# BA100_CPU_V1_0.net
KiCad netlist of a schematic drawn in Altium Designer
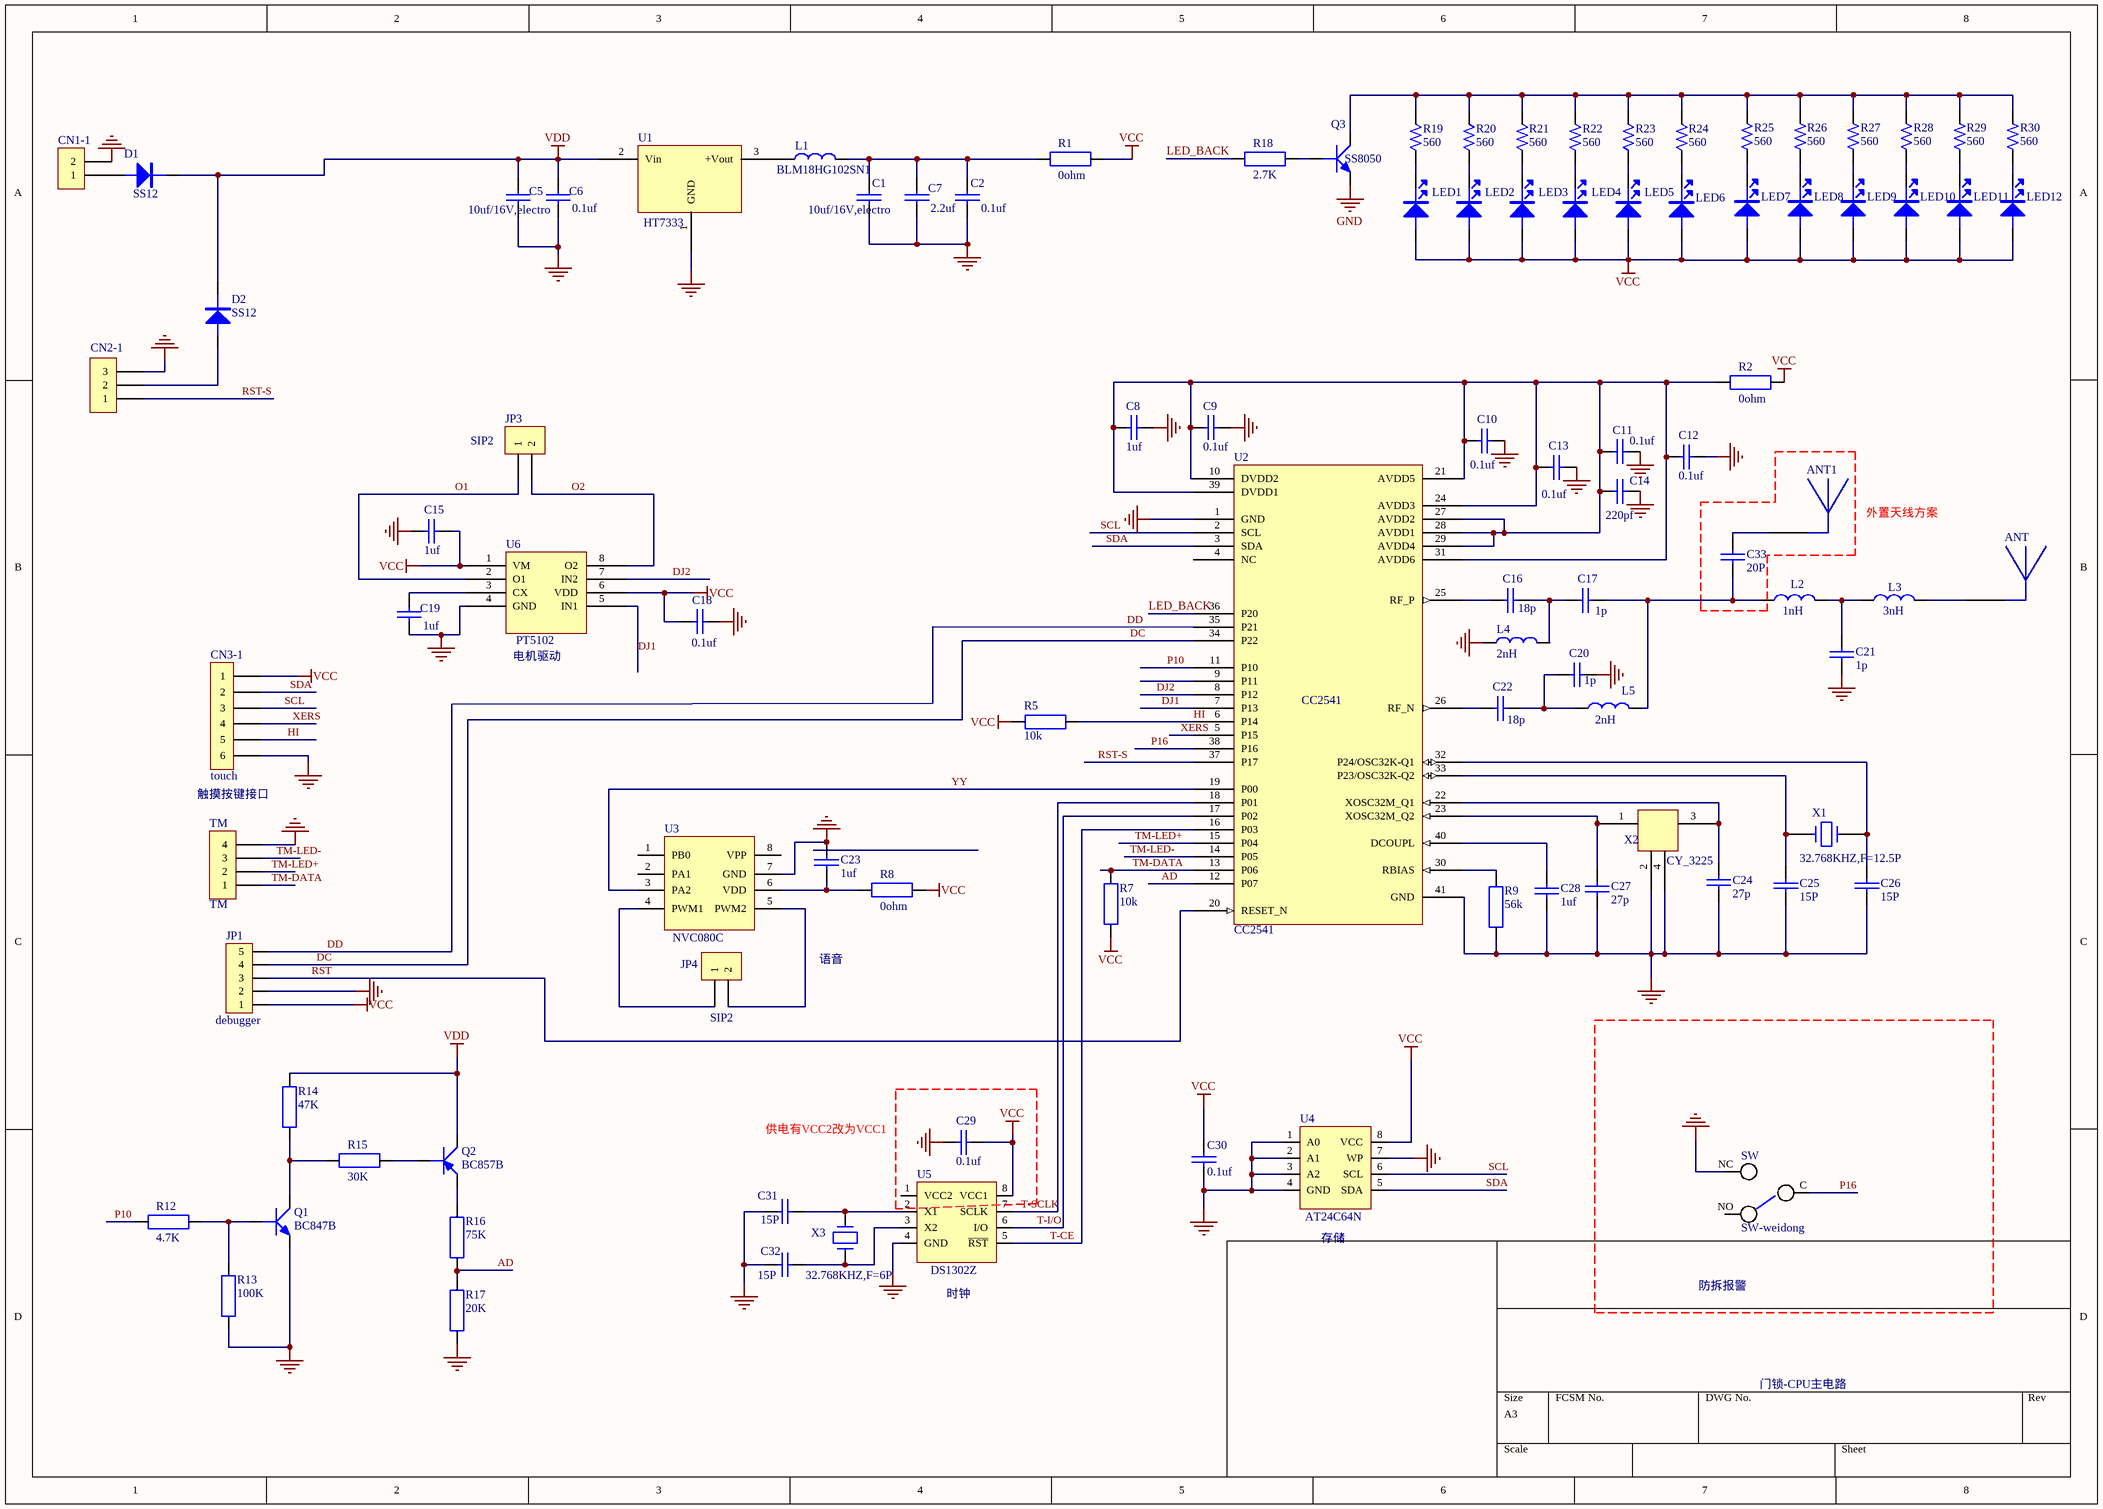
[diagram p0: BA100_CPU_V1.0.SchDoc]

(export (version "E")
  (design (tool "Eeschema 10.0.6"))
  (components
    (comp (ref "ANT") (value "ANT") (footprint "ANT") (libsource (lib "Schlib") (part "ANT")))
    (comp (ref "ANT1") (value "ANT") (footprint "IPEX") (libsource (lib "Schlib") (part "ANT")))
    (comp (ref "C1")
      (value "10uf/16V,electro")
      (footprint "ECAP_10U_4.3*4.3")
      (description "PC7-*****-KQA0A")
      (libsource (lib "Schlib") (part "PC7_0402_YAGEO"))
    )
    (comp (ref "C2")
      (value "0.1uf")
      (footprint "PCB标准封装库:PC7-*****-KO-0A_0603_TDK")
      (description "PC7-*****-KQA0A")
      (libsource (lib "Schlib") (part "PC7_0402_YAGEO"))
    )
    (comp (ref "C5")
      (value "10uf/16V,electro")
      (footprint "ECAP_10U_4.3*4.3")
      (description "PC7-*****-KQA0A")
      (libsource (lib "Schlib") (part "PC7_0402_YAGEO"))
    )
    (comp (ref "C6")
      (value "0.1uf")
      (footprint "PCB标准封装库:PC5-*****-**-0A_0603_TDK")
      (description "PC7-*****-KQA0A")
      (libsource (lib "Schlib") (part "PC7_0402_YAGEO"))
    )
    (comp (ref "C7")
      (value "2.2uf")
      (footprint "PCB标准封装库:PC5-*****-**-0A_0603_TDK")
      (description "PC7-*****-KQA0A")
      (libsource (lib "Schlib") (part "PC7_0402_YAGEO"))
    )
    (comp (ref "C8")
      (value "1uf")
      (footprint "PC5-*****-**-0A_0603_TDK")
      (description "PC7-*****-KQA0A")
      (libsource (lib "Schlib") (part "PC7_0402_YAGEO"))
    )
    (comp (ref "C9")
      (value "0.1uf")
      (footprint "PC7-*****-KO-0A_0603_TDK")
      (description "PC7-*****-KQA0A")
      (libsource (lib "Schlib") (part "PC7_0402_YAGEO"))
    )
    (comp (ref "C10")
      (value "0.1uf")
      (footprint "PC5-*****-**-0A_0603_TDK")
      (description "PC7-*****-KQA0A")
      (libsource (lib "Schlib") (part "PC7_0402_YAGEO"))
    )
    (comp (ref "C11")
      (value "0.1uf")
      (footprint "PC7-*****-KQA0A_0402_YAGEO")
      (description "PC7-*****-KQA0A")
      (libsource (lib "Schlib") (part "PC7_0402_YAGEO"))
    )
    (comp (ref "C12")
      (value "0.1uf")
      (footprint "PC7-*****-KQA0A_0402_YAGEO")
      (description "PC7-*****-KQA0A")
      (libsource (lib "Schlib") (part "PC7_0402_YAGEO"))
    )
    (comp (ref "C13")
      (value "0.1uf")
      (footprint "PC7-*****-KQA0A_0402_YAGEO")
      (description "PC7-*****-KQA0A")
      (libsource (lib "Schlib") (part "PC7_0402_YAGEO"))
    )
    (comp (ref "C14")
      (value "220pf")
      (footprint "PC7-*****-KQA0A_0402_YAGEO")
      (description "PC7-*****-KQA0A")
      (libsource (lib "Schlib") (part "PC7_0402_YAGEO"))
    )
    (comp (ref "C15")
      (value "1uf")
      (footprint "PCB标准封装库:PC5-*****-**-0A_0603_TDK")
      (description "PC7-*****-KQA0A")
      (libsource (lib "Schlib") (part "PC7_0402_YAGEO"))
    )
    (comp (ref "C16")
      (value "18p")
      (footprint "PC7-*****-KQA0A_0402_YAGEO")
      (description "PC7-*****-KQA0A")
      (libsource (lib "Schlib") (part "PC7_0402_YAGEO"))
    )
    (comp (ref "C17")
      (value "1p")
      (footprint "PC7-*****-KQA0A_0402_YAGEO")
      (description "PC7-*****-KQA0A")
      (libsource (lib "Schlib") (part "PC7_0402_YAGEO"))
    )
    (comp (ref "C18")
      (value "0.1uf")
      (footprint "PCB标准封装库:PC5-*****-**-0A_0603_TDK")
      (description "PC7-*****-KQA0A")
      (libsource (lib "Schlib") (part "PC7_0402_YAGEO"))
    )
    (comp (ref "C19")
      (value "1uf")
      (footprint "PCB标准封装库:PC5-*****-**-0A_0603_TDK")
      (description "PC7-*****-KQA0A")
      (libsource (lib "Schlib") (part "PC7_0402_YAGEO"))
    )
    (comp (ref "C20")
      (value "1p")
      (footprint "PC7-*****-KQA0A_0402_YAGEO")
      (description "PC7-*****-KQA0A")
      (libsource (lib "Schlib") (part "PC7_0402_YAGEO"))
    )
    (comp (ref "C21")
      (value "1p")
      (footprint "PC7-*****-KQA0A_0402_YAGEO")
      (description "PC7-*****-KQA0A")
      (libsource (lib "Schlib") (part "PC7_0402_YAGEO"))
    )
    (comp (ref "C22")
      (value "18p")
      (footprint "PC7-*****-KQA0A_0402_YAGEO")
      (description "PC7-*****-KQA0A")
      (libsource (lib "Schlib") (part "PC7_0402_YAGEO"))
    )
    (comp (ref "C23")
      (value "1uf")
      (footprint "PCB标准封装库:PC5-*****-**-0A_0603_TDK")
      (description "PC7-*****-KQA0A")
      (libsource (lib "Schlib") (part "PC7_0402_YAGEO"))
    )
    (comp (ref "C24")
      (value "27p")
      (footprint "PC7-*****-KO-0A_0603_TDK")
      (description "PC7-*****-KQA0A")
      (libsource (lib "Schlib") (part "PC7_0402_YAGEO"))
    )
    (comp (ref "C25")
      (value "15P")
      (footprint "PC5-*****-**-0A_0603_TDK")
      (description "PC7-*****-KQA0A")
      (libsource (lib "Schlib") (part "PC7_0402_YAGEO"))
    )
    (comp (ref "C26")
      (value "15P")
      (footprint "PC7-*****-KO-0A_0603_TDK")
      (description "PC7-*****-KQA0A")
      (libsource (lib "Schlib") (part "PC7_0402_YAGEO"))
    )
    (comp (ref "C27")
      (value "27p")
      (footprint "PC7-*****-KO-0A_0603_TDK")
      (description "PC7-*****-KQA0A")
      (libsource (lib "Schlib") (part "PC7_0402_YAGEO"))
    )
    (comp (ref "C28")
      (value "1uf")
      (footprint "PC5-*****-**-0A_0603_TDK")
      (description "PC7-*****-KQA0A")
      (libsource (lib "Schlib") (part "PC7_0402_YAGEO"))
    )
    (comp (ref "C29")
      (value "0.1uf")
      (footprint "PC7-*****-KO-0A_0603_TDK")
      (description "PC7-*****-KQA0A")
      (libsource (lib "Schlib") (part "PC7_0402_YAGEO"))
    )
    (comp (ref "C30")
      (value "0.1uf")
      (footprint "PC5-*****-**-0A_0603_TDK")
      (description "PC7-*****-KQA0A")
      (libsource (lib "Schlib") (part "PC7_0402_YAGEO"))
    )
    (comp (ref "C31")
      (value "15P")
      (footprint "PC7-*****-KO-0A_0603_TDK")
      (description "PC7-*****-KQA0A")
      (libsource (lib "Schlib") (part "PC7_0402_YAGEO"))
    )
    (comp (ref "C32")
      (value "15P")
      (footprint "PC7-*****-KO-0A_0603_TDK")
      (description "PC7-*****-KQA0A")
      (libsource (lib "Schlib") (part "PC7_0402_YAGEO"))
    )
    (comp (ref "C33")
      (value "20P")
      (footprint "PC7-*****-KQA0A_0402_YAGEO")
      (description "PC7-*****-KQA0A")
      (libsource (lib "Schlib") (part "PC7_0402_YAGEO"))
    )
    (comp (ref "CN1-1")
      (value "CN1")
      (footprint "PH2.0-2PIN-SMT")
      (description "Connector")
      (libsource (lib "") (part "CON2_1"))
    )
    (comp (ref "CN2-1")
      (value "CN2")
      (footprint "BJC:PH2.0-3PIN-SMT")
      (fields (field (name "PUBLISHER") "Altium Limited"))
      (libsource (lib "Schlib") (part "JP1_E524.03"))
    )
    (comp (ref "CN3-1") (value "touch") (footprint "PH1.25-6PIN-SMT") (libsource (lib "*") (part "CON6")))
    (comp (ref "D1")
      (value "SS12")
      (footprint "SS12-DIDEO")
      (description "PDD-00330-00-2A")
      (libsource (lib "*") (part "PDD_SD101CWS"))
    )
    (comp (ref "D2")
      (value "SS12")
      (footprint "SS12-DIDEO")
      (description "PDD-00330-00-2A")
      (libsource (lib "*") (part "PDD_SD101CWS"))
    )
    (comp (ref "JP1") (value "debugger") (footprint "ISCP-5PIN") (libsource (lib "BJC") (part "CON5")))
    (comp (ref "JP3")
      (value "SIP2")
      (footprint "PH2.0-2PIN-LSMT1")
      (description "Connector")
      (libsource (lib "BJC") (part "CON2"))
    )
    (comp (ref "JP4")
      (value "SIP2")
      (footprint "PH2.0-2PIN-LSMT1")
      (description "Connector")
      (libsource (lib "BJC") (part "CON2"))
    )
    (comp (ref "L1")
      (value "BLM18HG102SN1")
      (footprint "PCB标准封装库:PC7-*****-KO-0A_0603_TDK")
      (description "PWL-00195-00-20")
      (libsource (lib "Schlib") (part "PWL_18nH"))
    )
    (comp (ref "L2")
      (value "1nH")
      (footprint "PC5-*****-**-0A_0402_TDK")
      (description "PWL-00195-00-20")
      (libsource (lib "Schlib") (part "PWL_18nH"))
    )
    (comp (ref "L3")
      (value "3nH")
      (footprint "PCB标准封装库:PC5-*****-**-0A_0402_TDK")
      (description "PWL-00195-00-20")
      (libsource (lib "Schlib") (part "PWL_18nH"))
    )
    (comp (ref "L4")
      (value "2nH")
      (footprint "PC5-*****-**-0A_0402_TDK")
      (description "PWL-00195-00-20")
      (libsource (lib "Schlib") (part "PWL_18nH"))
    )
    (comp (ref "L5")
      (value "2nH")
      (footprint "PC5-*****-**-0A_0402_TDK")
      (description "PWL-00195-00-20")
      (libsource (lib "Schlib") (part "PWL_18nH"))
    )
    (comp (ref "LED1")
      (value "MA2X335")
      (footprint "PCB_100:LED-0805")
      (description "LED")
      (libsource (lib "PCB_BA100") (part "PDD_MA2X335"))
    )
    (comp (ref "LED2")
      (value "MA2X335")
      (footprint "PCB_100:LED-0805")
      (description "LED")
      (libsource (lib "PCB_BA100") (part "PDD_MA2X335"))
    )
    (comp (ref "LED3")
      (value "MA2X335")
      (footprint "PCB_100:LED-0805")
      (description "LED")
      (libsource (lib "PCB_BA100") (part "PDD_MA2X335"))
    )
    (comp (ref "LED4")
      (value "MA2X335")
      (footprint "PCB_100:LED-0805")
      (description "LED")
      (libsource (lib "PCB_BA100") (part "PDD_MA2X335"))
    )
    (comp (ref "LED5")
      (value "MA2X335")
      (footprint "PCB_100:LED-0805")
      (description "LED")
      (libsource (lib "PCB_BA100") (part "PDD_MA2X335"))
    )
    (comp (ref "LED6")
      (value "MA2X335")
      (footprint "PCB_100:LED-0805")
      (description "LED")
      (libsource (lib "PCB_BA100") (part "PDD_MA2X335"))
    )
    (comp (ref "LED7")
      (value "MA2X335")
      (footprint "BA100_CPU_V1.5.1:LED-0805")
      (description "LED")
      (libsource (lib "BA100_CPU_1.5.1") (part "PDD_MA2X335"))
    )
    (comp (ref "LED8")
      (value "MA2X335")
      (footprint "BA100_CPU_V1.5.1:LED-0805")
      (description "LED")
      (libsource (lib "BA100_CPU_1.5.1") (part "PDD_MA2X335"))
    )
    (comp (ref "LED9")
      (value "MA2X335")
      (footprint "BA100_CPU_V1.5.1:LED-0805")
      (description "LED")
      (libsource (lib "BA100_CPU_1.5.1") (part "PDD_MA2X335"))
    )
    (comp (ref "LED10")
      (value "MA2X335")
      (footprint "BA100_CPU_V1.5.1:LED-0805")
      (description "LED")
      (libsource (lib "BA100_CPU_1.5.1") (part "PDD_MA2X335"))
    )
    (comp (ref "LED11")
      (value "MA2X335")
      (footprint "BA100_CPU_V1.5.1:LED-0805")
      (description "LED")
      (libsource (lib "BA100_CPU_1.5.1") (part "PDD_MA2X335"))
    )
    (comp (ref "LED12")
      (value "MA2X335")
      (footprint "BA100_CPU_V1.5.1:LED-0805")
      (description "LED")
      (libsource (lib "BA100_CPU_1.5.1") (part "PDD_MA2X335"))
    )
    (comp (ref "Q1")
      (value "BC847B")
      (footprint "PTR-C0025-00-2A_2SC1623")
      (description "PTR-C0028-00-2A")
      (libsource (lib "Schlib") (part "PTR_2SC3356"))
    )
    (comp (ref "Q2")
      (value "BC857B")
      (footprint "PTR-C0025-00-2A_2SC1623")
      (libsource (lib "*") (part "PTR-PNP"))
    )
    (comp (ref "Q3")
      (value "SS8050")
      (footprint "BA100_CPU_V1.4.0:PTR-C0025-00-2A_2SC1623")
      (description "PTR-C0230-00-20**")
      (libsource (lib "Schlib") (part "PTR_2SC5344SF-Y"))
    )
    (comp (ref "R1")
      (value "0ohm")
      (footprint "PCB标准封装库:PRC-*****-AM-0A_0603")
      (description "PRC-*****-AM-0A_0603")
      (libsource (lib "Schlib") (part "PRC_0603"))
    )
    (comp (ref "R2")
      (value "0ohm")
      (footprint "PRC-*****-AM-0A_0603")
      (description "PRC-*****-AM-0A_0603")
      (libsource (lib "Schlib") (part "PRC_0603"))
    )
    (comp (ref "R5")
      (value "10k")
      (footprint "PCB标准封装库:PRC-*****-AM-0A_0603")
      (description "PRC-*****-AM-0A_0603")
      (libsource (lib "Schlib") (part "PRC_0603"))
    )
    (comp (ref "R7")
      (value "10k")
      (footprint "PCB标准封装库:PRC-*****-AM-0A_0603")
      (description "PRC-*****-AM-0A_0603")
      (libsource (lib "Schlib") (part "PRC_0603"))
    )
    (comp (ref "R8")
      (value "0ohm")
      (footprint "PCB标准封装库:PRC-*****-AM-0A_0603")
      (description "PRC-*****-AM-0A_0603")
      (libsource (lib "Schlib") (part "PRC_0603"))
    )
    (comp (ref "R9")
      (value "56k")
      (footprint "PRC-*****-BM-0A_0402")
      (description "PRC-*****-AM-0A_0603")
      (libsource (lib "Schlib") (part "PRC_0603"))
    )
    (comp (ref "R12")
      (value "4.7K")
      (footprint "PCB标准封装库:PRC-*****-AM-0A_0603")
      (description "PRC-*****-AM-0A_0603")
      (libsource (lib "Schlib") (part "PRC_0603"))
    )
    (comp (ref "R13")
      (value "100K")
      (footprint "PCB标准封装库:PRC-*****-AM-0A_0603")
      (description "PRC-*****-AM-0A_0603")
      (libsource (lib "Schlib") (part "PRC_0603"))
    )
    (comp (ref "R14")
      (value "47K")
      (footprint "PCB标准封装库:PRC-*****-AM-0A_0603")
      (description "PRC-*****-AM-0A_0603")
      (libsource (lib "Schlib") (part "PRC_0603"))
    )
    (comp (ref "R15")
      (value "30K")
      (footprint "BA100_CPU_V1.4.0:PRC-*****-AM-0A_0603")
      (description "PRC-*****-AM-0A_0603")
      (libsource (lib "Schlib") (part "PRC_0603"))
    )
    (comp (ref "R16")
      (value "75K")
      (footprint "PCB标准封装库:PRC-*****-AM-0A_0603")
      (description "PRC-*****-AM-0A_0603")
      (libsource (lib "Schlib") (part "PRC_0603"))
    )
    (comp (ref "R17")
      (value "20K")
      (footprint "PCB标准封装库:PRC-*****-AM-0A_0603")
      (description "PRC-*****-AM-0A_0603")
      (libsource (lib "Schlib") (part "PRC_0603"))
    )
    (comp (ref "R18")
      (value "2.7K")
      (footprint "BA100_CPU_V1.4.0:PRC-*****-AM-0A_0603")
      (description "PRC-*****-AM-0A_0603")
      (libsource (lib "Schlib") (part "PRC_0603"))
    )
    (comp (ref "R19")
      (value "560")
      (footprint "PRC-*****-AM-0A_0603")
      (libsource (lib "PCB_BA100") (part "RES"))
    )
    (comp (ref "R20")
      (value "560")
      (footprint "PRC-*****-AM-0A_0603")
      (libsource (lib "PCB_BA100") (part "RES"))
    )
    (comp (ref "R21")
      (value "560")
      (footprint "PRC-*****-AM-0A_0603")
      (libsource (lib "PCB_BA100") (part "RES"))
    )
    (comp (ref "R22")
      (value "560")
      (footprint "PRC-*****-AM-0A_0603")
      (libsource (lib "PCB_BA100") (part "RES"))
    )
    (comp (ref "R23")
      (value "560")
      (footprint "PRC-*****-AM-0A_0603")
      (libsource (lib "PCB_BA100") (part "RES"))
    )
    (comp (ref "R24")
      (value "560")
      (footprint "PRC-*****-AM-0A_0603")
      (libsource (lib "PCB_BA100") (part "RES"))
    )
    (comp (ref "R25")
      (value "560")
      (footprint "BA100_CPU_V1.5.1:PRC-*****-AM-0A_0603")
      (libsource (lib "BA100_CPU_1.5.1") (part "RES"))
    )
    (comp (ref "R26")
      (value "560")
      (footprint "BA100_CPU_V1.5.1:PRC-*****-AM-0A_0603")
      (libsource (lib "BA100_CPU_1.5.1") (part "RES"))
    )
    (comp (ref "R27")
      (value "560")
      (footprint "BA100_CPU_V1.5.1:PRC-*****-AM-0A_0603")
      (libsource (lib "BA100_CPU_1.5.1") (part "RES"))
    )
    (comp (ref "R28")
      (value "560")
      (footprint "BA100_CPU_V1.5.1:PRC-*****-AM-0A_0603")
      (libsource (lib "BA100_CPU_1.5.1") (part "RES"))
    )
    (comp (ref "R29")
      (value "560")
      (footprint "BA100_CPU_V1.5.1:PRC-*****-AM-0A_0603")
      (libsource (lib "BA100_CPU_1.5.1") (part "RES"))
    )
    (comp (ref "R30")
      (value "560")
      (footprint "BA100_CPU_V1.5.1:PRC-*****-AM-0A_0603")
      (libsource (lib "BA100_CPU_1.5.1") (part "RES"))
    )
    (comp (ref "SW")
      (value "SW-weidong")
      (footprint "SW-weidong")
      (libsource (lib "PCB_BA100_MAIN_1.5.1") (part "SW-weidong"))
    )
    (comp (ref "TM") (value "TM") (footprint "PH2.0-4PIN-SMT") (libsource (lib "Schlib") (part "HDR1X4 ***")))
    (comp (ref "U1") (value "HT7333") (footprint "SOT89") (libsource (lib "*") (part "LM117K")))
    (comp (ref "U2") (value "CC2541") (footprint "CC2530_QFN40") (libsource (lib "*") (part "CC2541")))
    (comp (ref "U3") (value "NVC080C") (footprint "SOP-8") (libsource (lib "BJC") (part "NV040C")))
    (comp (ref "U4")
      (value "AT24C64N")
      (footprint "PIC-00570-40-2A_93LC46B")
      (libsource (lib "BJC") (part "AT24C64N"))
    )
    (comp (ref "U5")
      (value "DS1302Z")
      (footprint "PIC-00570-40-2A_93LC46B")
      (libsource (lib "BJC") (part "DS1302"))
    )
    (comp (ref "U6") (value "PT5102") (footprint "PT5102") (libsource (lib "BJC") (part "Component_1_1")))
    (comp (ref "X1")
      (value "32.768KHZ,F=12.5P")
      (footprint "FC-135")
      (description "Crystal")
      (libsource (lib "CC254xEM原理图库") (part "CRYSTAL"))
    )
    (comp (ref "X2")
      (value "CY_3225")
      (footprint "CY_3225")
      (libsource (lib "CC254xEM原理图库") (part "CY_3225"))
    )
    (comp (ref "X3")
      (value "32.768KHZ,F=6P")
      (footprint "GUASUO-V1.3-151210:FC-135")
      (description "PTR-X0320-20-2A")
      (libsource (lib "BJC") (part "PTR_16MHZ"))
    )
  )
  (nets
    (net (code "1") (name "/AD") (class "Default")
      (node (ref "R16") (pin "1") (pinfunction "1_1") (pintype "passive"))
      (node (ref "R17") (pin "2") (pinfunction "2_2") (pintype "passive"))
      (node (ref "U2") (pin "12") (pinfunction "P07_12") (pintype "passive"))
    )
    (net (code "2") (name "/DC") (class "Default")
      (node (ref "JP1") (pin "4") (pinfunction "4_4") (pintype "passive"))
      (node (ref "U2") (pin "34") (pinfunction "P22_34") (pintype "passive"))
    )
    (net (code "3") (name "/DD") (class "Default")
      (node (ref "JP1") (pin "5") (pinfunction "5_5") (pintype "passive"))
      (node (ref "U2") (pin "35") (pinfunction "P21_35") (pintype "passive"))
    )
    (net (code "4") (name "/DJ1") (class "Default")
      (node (ref "U2") (pin "7") (pinfunction "P13_7") (pintype "passive"))
      (node (ref "U6") (pin "5") (pinfunction "IN1_5") (pintype "passive"))
    )
    (net (code "5") (name "/DJ2") (class "Default")
      (node (ref "U2") (pin "8") (pinfunction "P12_8") (pintype "passive"))
      (node (ref "U6") (pin "7") (pinfunction "IN2_7") (pintype "passive"))
    )
    (net (code "6") (name "/HI") (class "Default")
      (node (ref "CN3-1") (pin "5") (pinfunction "5_5") (pintype "passive"))
      (node (ref "R5") (pin "2") (pinfunction "2_2") (pintype "passive"))
      (node (ref "U2") (pin "6") (pinfunction "P14_6") (pintype "passive"))
    )
    (net (code "7") (name "/LED_BACK") (class "Default")
      (node (ref "R18") (pin "1") (pinfunction "1_1") (pintype "passive"))
      (node (ref "U2") (pin "36") (pinfunction "P20_36") (pintype "passive"))
    )
    (net (code "8") (name "/O1") (class "Default")
      (node (ref "JP3") (pin "1") (pinfunction "1_1") (pintype "passive"))
      (node (ref "U6") (pin "2") (pinfunction "O1_2") (pintype "passive"))
    )
    (net (code "9") (name "/O2") (class "Default")
      (node (ref "JP3") (pin "2") (pinfunction "2_2") (pintype "passive"))
      (node (ref "U6") (pin "8") (pinfunction "O2_8") (pintype "passive"))
    )
    (net (code "10") (name "/P10") (class "Default")
      (node (ref "R12") (pin "1") (pinfunction "1_1") (pintype "passive"))
      (node (ref "U2") (pin "11") (pinfunction "P10_11") (pintype "passive"))
    )
    (net (code "11") (name "/P16") (class "Default")
      (node (ref "SW") (pin "C") (pinfunction "1_C") (pintype "passive"))
      (node (ref "U2") (pin "38") (pinfunction "P16_38") (pintype "passive"))
    )
    (net (code "12") (name "/RST") (class "Default")
      (node (ref "JP1") (pin "3") (pinfunction "3_3") (pintype "passive"))
      (node (ref "U2") (pin "20") (pinfunction "RESET_N_20") (pintype "input"))
    )
    (net (code "13") (name "/RST-S") (class "Default")
      (node (ref "CN2-1") (pin "1") (pinfunction "1_1") (pintype "passive"))
      (node (ref "U2") (pin "37") (pinfunction "P17_37") (pintype "passive"))
    )
    (net (code "14") (name "/SCL") (class "Default")
      (node (ref "CN3-1") (pin "3") (pinfunction "3_3") (pintype "passive"))
      (node (ref "U2") (pin "2") (pinfunction "SCL_2") (pintype "power_in"))
      (node (ref "U4") (pin "6") (pinfunction "SCL_6") (pintype "passive"))
    )
    (net (code "15") (name "/SDA") (class "Default")
      (node (ref "CN3-1") (pin "2") (pinfunction "2_2") (pintype "passive"))
      (node (ref "U2") (pin "3") (pinfunction "SDA_3") (pintype "power_in"))
      (node (ref "U4") (pin "5") (pinfunction "SDA_5") (pintype "passive"))
    )
    (net (code "16") (name "/T-CE") (class "Default")
      (node (ref "U2") (pin "16") (pinfunction "P03_16") (pintype "passive"))
      (node (ref "U5") (pin "5") (pinfunction "~{RST}_5") (pintype "passive"))
    )
    (net (code "17") (name "/T-I{slash}O") (class "Default")
      (node (ref "U2") (pin "17") (pinfunction "P02_17") (pintype "passive"))
      (node (ref "U5") (pin "6") (pinfunction "I/O_6") (pintype "passive"))
    )
    (net (code "18") (name "/T-SCLK") (class "Default")
      (node (ref "U2") (pin "18") (pinfunction "P01_18") (pintype "passive"))
      (node (ref "U5") (pin "7") (pinfunction "SCLK_7") (pintype "passive"))
    )
    (net (code "19") (name "/TM-DATA") (class "Default")
      (node (ref "R7") (pin "2") (pinfunction "2_2") (pintype "passive"))
      (node (ref "TM") (pin "1") (pinfunction "1_1") (pintype "passive"))
      (node (ref "U2") (pin "13") (pinfunction "P06_13") (pintype "passive"))
    )
    (net (code "20") (name "/TM-LED+") (class "Default")
      (node (ref "TM") (pin "2") (pinfunction "2_2") (pintype "passive"))
      (node (ref "U2") (pin "15") (pinfunction "P04_15") (pintype "passive"))
    )
    (net (code "21") (name "/TM-LED-") (class "Default")
      (node (ref "TM") (pin "3") (pinfunction "3_3") (pintype "passive"))
      (node (ref "U2") (pin "14") (pinfunction "P05_14") (pintype "passive"))
    )
    (net (code "22") (name "/XERS") (class "Default")
      (node (ref "CN3-1") (pin "4") (pinfunction "4_4") (pintype "passive"))
      (node (ref "U2") (pin "5") (pinfunction "P15_5") (pintype "passive"))
    )
    (net (code "23") (name "/YY") (class "Default")
      (node (ref "U2") (pin "19") (pinfunction "P00_19") (pintype "passive"))
      (node (ref "U3") (pin "3") (pinfunction "PA2_3") (pintype "passive"))
    )
    (net (code "24") (name "GND") (class "Default")
      (node (ref "C1") (pin "1") (pinfunction "1_1") (pintype "passive"))
      (node (ref "C10") (pin "2") (pinfunction "2_2") (pintype "passive"))
      (node (ref "C11") (pin "2") (pinfunction "2_2") (pintype "passive"))
      (node (ref "C12") (pin "2") (pinfunction "2_2") (pintype "passive"))
      (node (ref "C13") (pin "2") (pinfunction "2_2") (pintype "passive"))
      (node (ref "C14") (pin "1") (pinfunction "1_1") (pintype "passive"))
      (node (ref "C15") (pin "1") (pinfunction "1_1") (pintype "passive"))
      (node (ref "C18") (pin "1") (pinfunction "1_1") (pintype "passive"))
      (node (ref "C19") (pin "1") (pinfunction "1_1") (pintype "passive"))
      (node (ref "C2") (pin "1") (pinfunction "1_1") (pintype "passive"))
      (node (ref "C20") (pin "2") (pinfunction "2_2") (pintype "passive"))
      (node (ref "C21") (pin "1") (pinfunction "1_1") (pintype "passive"))
      (node (ref "C23") (pin "2") (pinfunction "2_2") (pintype "passive"))
      (node (ref "C24") (pin "1") (pinfunction "1_1") (pintype "passive"))
      (node (ref "C25") (pin "1") (pinfunction "1_1") (pintype "passive"))
      (node (ref "C26") (pin "1") (pinfunction "1_1") (pintype "passive"))
      (node (ref "C27") (pin "1") (pinfunction "1_1") (pintype "passive"))
      (node (ref "C28") (pin "1") (pinfunction "1_1") (pintype "passive"))
      (node (ref "C29") (pin "2") (pinfunction "2_2") (pintype "passive"))
      (node (ref "C30") (pin "1") (pinfunction "1_1") (pintype "passive"))
      (node (ref "C31") (pin "2") (pinfunction "2_2") (pintype "passive"))
      (node (ref "C32") (pin "2") (pinfunction "2_2") (pintype "passive"))
      (node (ref "C5") (pin "1") (pinfunction "1_1") (pintype "passive"))
      (node (ref "C6") (pin "1") (pinfunction "1_1") (pintype "passive"))
      (node (ref "C7") (pin "2") (pinfunction "2_2") (pintype "passive"))
      (node (ref "C8") (pin "2") (pinfunction "2_2") (pintype "passive"))
      (node (ref "C9") (pin "2") (pinfunction "2_2") (pintype "passive"))
      (node (ref "CN1-1") (pin "2") (pinfunction "2_2") (pintype "passive"))
      (node (ref "CN2-1") (pin "3") (pinfunction "3_3") (pintype "passive"))
      (node (ref "CN3-1") (pin "6") (pinfunction "6_6") (pintype "passive"))
      (node (ref "JP1") (pin "2") (pinfunction "2_2") (pintype "passive"))
      (node (ref "L4") (pin "1") (pintype "passive"))
      (node (ref "Q1") (pin "E") (pinfunction "1_E") (pintype "passive"))
      (node (ref "Q3") (pin "E") (pinfunction "2_E") (pintype "passive"))
      (node (ref "R13") (pin "1") (pinfunction "1_1") (pintype "passive"))
      (node (ref "R17") (pin "1") (pinfunction "1_1") (pintype "passive"))
      (node (ref "R9") (pin "2") (pinfunction "2_2") (pintype "passive"))
      (node (ref "SW") (pin "NC") (pinfunction "3_NC") (pintype "passive"))
      (node (ref "TM") (pin "4") (pinfunction "4_4") (pintype "passive"))
      (node (ref "U1") (pin "1") (pinfunction "GND_1") (pintype "passive"))
      (node (ref "U2") (pin "1") (pinfunction "GND_1") (pintype "power_in"))
      (node (ref "U2") (pin "41") (pinfunction "GND_41") (pintype "power_in"))
      (node (ref "U3") (pin "7") (pinfunction "GND_7") (pintype "passive"))
      (node (ref "U4") (pin "1") (pinfunction "A0_1") (pintype "passive"))
      (node (ref "U4") (pin "2") (pinfunction "A1_2") (pintype "passive"))
      (node (ref "U4") (pin "3") (pinfunction "A2_3") (pintype "passive"))
      (node (ref "U4") (pin "4") (pinfunction "GND_4") (pintype "passive"))
      (node (ref "U4") (pin "7") (pinfunction "WP_7") (pintype "passive"))
      (node (ref "U5") (pin "4") (pinfunction "GND_4") (pintype "passive"))
      (node (ref "U6") (pin "4") (pinfunction "GND_4") (pintype "passive"))
      (node (ref "X2") (pin "2") (pinfunction "2_2") (pintype "power_in"))
      (node (ref "X2") (pin "4") (pinfunction "4_4") (pintype "power_in"))
    )
    (net (code "25") (name "Net-(ANT-Pad1)") (class "Default")
      (node (ref "ANT") (pin "1") (pinfunction "1_1") (pintype "passive"))
      (node (ref "L3") (pin "2") (pintype "passive"))
    )
    (net (code "26") (name "Net-(ANT1-Pad1)") (class "Default")
      (node (ref "ANT1") (pin "1") (pinfunction "1_1") (pintype "passive"))
      (node (ref "C33") (pin "2") (pinfunction "2_2") (pintype "passive"))
    )
    (net (code "27") (name "Net-(C1-Pad2)") (class "Default")
      (node (ref "C1") (pin "2") (pinfunction "2_2") (pintype "passive"))
      (node (ref "C2") (pin "2") (pinfunction "2_2") (pintype "passive"))
      (node (ref "C7") (pin "1") (pinfunction "1_1") (pintype "passive"))
      (node (ref "L1") (pin "2") (pintype "passive"))
      (node (ref "R1") (pin "1") (pinfunction "1_1") (pintype "passive"))
    )
    (net (code "28") (name "Net-(C16-Pad2)") (class "Default")
      (node (ref "C16") (pin "2") (pinfunction "2_2") (pintype "passive"))
      (node (ref "C17") (pin "1") (pinfunction "1_1") (pintype "passive"))
      (node (ref "L4") (pin "2") (pintype "passive"))
    )
    (net (code "29") (name "Net-(C17-Pad2)") (class "Default")
      (node (ref "C17") (pin "2") (pinfunction "2_2") (pintype "passive"))
      (node (ref "C33") (pin "1") (pinfunction "1_1") (pintype "passive"))
      (node (ref "L2") (pin "1") (pintype "passive"))
      (node (ref "L5") (pin "2") (pintype "passive"))
    )
    (net (code "30") (name "Net-(C20-Pad1)") (class "Default")
      (node (ref "C20") (pin "1") (pinfunction "1_1") (pintype "passive"))
      (node (ref "C22") (pin "2") (pinfunction "2_2") (pintype "passive"))
      (node (ref "L5") (pin "1") (pintype "passive"))
    )
    (net (code "31") (name "Net-(C21-Pad2)") (class "Default")
      (node (ref "C21") (pin "2") (pinfunction "2_2") (pintype "passive"))
      (node (ref "L2") (pin "2") (pintype "passive"))
      (node (ref "L3") (pin "1") (pintype "passive"))
    )
    (net (code "32") (name "Net-(CN1-1-Pad1)") (class "Default")
      (node (ref "CN1-1") (pin "1") (pinfunction "1_1") (pintype "passive"))
      (node (ref "D1") (pin "2") (pinfunction "2_2") (pintype "passive"))
    )
    (net (code "33") (name "Net-(CN2-1-Pad2)") (class "Default")
      (node (ref "CN2-1") (pin "2") (pinfunction "2_2") (pintype "passive"))
      (node (ref "D2") (pin "2") (pinfunction "2_2") (pintype "passive"))
    )
    (net (code "34") (name "Net-(D1-Pad1)") (class "Default")
      (node (ref "D1") (pin "1") (pinfunction "1_1") (pintype "passive"))
    )
    (net (code "35") (name "Net-(D1-Pad2)") (class "Default")
      (node (ref "D1") (pin "2") (pinfunction "2_2") (pintype "passive"))
    )
    (net (code "36") (name "Net-(D2-Pad1)") (class "Default")
      (node (ref "D2") (pin "1") (pinfunction "1_1") (pintype "passive"))
    )
    (net (code "37") (name "Net-(D2-Pad2)") (class "Default")
      (node (ref "D2") (pin "2") (pinfunction "2_2") (pintype "passive"))
    )
    (net (code "38") (name "Net-(LED1-2-PadC)") (class "Default")
      (node (ref "LED1") (pin "C") (pinfunction "2_C") (pintype "passive"))
      (node (ref "R19") (pin "1") (pinfunction "1_1") (pintype "passive"))
    )
    (net (code "39") (name "Net-(LED1-Pad1)") (class "Default")
      (node (ref "LED1") (pin "1") (pinfunction "1_1") (pintype "passive"))
    )
    (net (code "40") (name "Net-(LED1-Pad2)") (class "Default")
      (node (ref "LED1") (pin "2") (pinfunction "2_2") (pintype "passive"))
    )
    (net (code "41") (name "Net-(LED2-2-PadC)") (class "Default")
      (node (ref "LED2") (pin "C") (pinfunction "2_C") (pintype "passive"))
      (node (ref "R20") (pin "1") (pinfunction "1_1") (pintype "passive"))
    )
    (net (code "42") (name "Net-(LED2-Pad1)") (class "Default")
      (node (ref "LED2") (pin "1") (pinfunction "1_1") (pintype "passive"))
    )
    (net (code "43") (name "Net-(LED2-Pad2)") (class "Default")
      (node (ref "LED2") (pin "2") (pinfunction "2_2") (pintype "passive"))
    )
    (net (code "44") (name "Net-(LED3-2-PadC)") (class "Default")
      (node (ref "LED3") (pin "C") (pinfunction "2_C") (pintype "passive"))
      (node (ref "R21") (pin "1") (pinfunction "1_1") (pintype "passive"))
    )
    (net (code "45") (name "Net-(LED3-Pad1)") (class "Default")
      (node (ref "LED3") (pin "1") (pinfunction "1_1") (pintype "passive"))
    )
    (net (code "46") (name "Net-(LED3-Pad2)") (class "Default")
      (node (ref "LED3") (pin "2") (pinfunction "2_2") (pintype "passive"))
    )
    (net (code "47") (name "Net-(LED4-2-PadC)") (class "Default")
      (node (ref "LED4") (pin "C") (pinfunction "2_C") (pintype "passive"))
      (node (ref "R22") (pin "1") (pinfunction "1_1") (pintype "passive"))
    )
    (net (code "48") (name "Net-(LED4-Pad1)") (class "Default")
      (node (ref "LED4") (pin "1") (pinfunction "1_1") (pintype "passive"))
    )
    (net (code "49") (name "Net-(LED4-Pad2)") (class "Default")
      (node (ref "LED4") (pin "2") (pinfunction "2_2") (pintype "passive"))
    )
    (net (code "50") (name "Net-(LED5-2-PadC)") (class "Default")
      (node (ref "LED5") (pin "C") (pinfunction "2_C") (pintype "passive"))
      (node (ref "R23") (pin "1") (pinfunction "1_1") (pintype "passive"))
    )
    (net (code "51") (name "Net-(LED5-Pad1)") (class "Default")
      (node (ref "LED5") (pin "1") (pinfunction "1_1") (pintype "passive"))
    )
    (net (code "52") (name "Net-(LED5-Pad2)") (class "Default")
      (node (ref "LED5") (pin "2") (pinfunction "2_2") (pintype "passive"))
    )
    (net (code "53") (name "Net-(LED6-2-PadC)") (class "Default")
      (node (ref "LED6") (pin "C") (pinfunction "2_C") (pintype "passive"))
      (node (ref "R24") (pin "1") (pinfunction "1_1") (pintype "passive"))
    )
    (net (code "54") (name "Net-(LED6-Pad1)") (class "Default")
      (node (ref "LED6") (pin "1") (pinfunction "1_1") (pintype "passive"))
    )
    (net (code "55") (name "Net-(LED6-Pad2)") (class "Default")
      (node (ref "LED6") (pin "2") (pinfunction "2_2") (pintype "passive"))
    )
    (net (code "56") (name "Net-(LED7-2-PadC)") (class "Default")
      (node (ref "LED7") (pin "C") (pinfunction "2_C") (pintype "passive"))
      (node (ref "R25") (pin "1") (pinfunction "1_1") (pintype "passive"))
    )
    (net (code "57") (name "Net-(LED7-Pad1)") (class "Default")
      (node (ref "LED7") (pin "1") (pinfunction "1_1") (pintype "passive"))
    )
    (net (code "58") (name "Net-(LED7-Pad2)") (class "Default")
      (node (ref "LED7") (pin "2") (pinfunction "2_2") (pintype "passive"))
    )
    (net (code "59") (name "Net-(LED8-2-PadC)") (class "Default")
      (node (ref "LED8") (pin "C") (pinfunction "2_C") (pintype "passive"))
      (node (ref "R26") (pin "1") (pinfunction "1_1") (pintype "passive"))
    )
    (net (code "60") (name "Net-(LED8-Pad1)") (class "Default")
      (node (ref "LED8") (pin "1") (pinfunction "1_1") (pintype "passive"))
    )
    (net (code "61") (name "Net-(LED8-Pad2)") (class "Default")
      (node (ref "LED8") (pin "2") (pinfunction "2_2") (pintype "passive"))
    )
    (net (code "62") (name "Net-(LED9-2-PadC)") (class "Default")
      (node (ref "LED9") (pin "C") (pinfunction "2_C") (pintype "passive"))
      (node (ref "R27") (pin "1") (pinfunction "1_1") (pintype "passive"))
    )
    (net (code "63") (name "Net-(LED9-Pad1)") (class "Default")
      (node (ref "LED9") (pin "1") (pinfunction "1_1") (pintype "passive"))
    )
    (net (code "64") (name "Net-(LED9-Pad2)") (class "Default")
      (node (ref "LED9") (pin "2") (pinfunction "2_2") (pintype "passive"))
    )
    (net (code "65") (name "Net-(LED10-2-PadC)") (class "Default")
      (node (ref "LED10") (pin "C") (pinfunction "2_C") (pintype "passive"))
      (node (ref "R28") (pin "1") (pinfunction "1_1") (pintype "passive"))
    )
    (net (code "66") (name "Net-(LED10-Pad1)") (class "Default")
      (node (ref "LED10") (pin "1") (pinfunction "1_1") (pintype "passive"))
    )
    (net (code "67") (name "Net-(LED10-Pad2)") (class "Default")
      (node (ref "LED10") (pin "2") (pinfunction "2_2") (pintype "passive"))
    )
    (net (code "68") (name "Net-(LED11-2-PadC)") (class "Default")
      (node (ref "LED11") (pin "C") (pinfunction "2_C") (pintype "passive"))
      (node (ref "R29") (pin "1") (pinfunction "1_1") (pintype "passive"))
    )
    (net (code "69") (name "Net-(LED11-Pad1)") (class "Default")
      (node (ref "LED11") (pin "1") (pinfunction "1_1") (pintype "passive"))
    )
    (net (code "70") (name "Net-(LED11-Pad2)") (class "Default")
      (node (ref "LED11") (pin "2") (pinfunction "2_2") (pintype "passive"))
    )
    (net (code "71") (name "Net-(LED12-2-PadC)") (class "Default")
      (node (ref "LED12") (pin "C") (pinfunction "2_C") (pintype "passive"))
      (node (ref "R30") (pin "1") (pinfunction "1_1") (pintype "passive"))
    )
    (net (code "72") (name "Net-(LED12-Pad1)") (class "Default")
      (node (ref "LED12") (pin "1") (pinfunction "1_1") (pintype "passive"))
    )
    (net (code "73") (name "Net-(LED12-Pad2)") (class "Default")
      (node (ref "LED12") (pin "2") (pinfunction "2_2") (pintype "passive"))
    )
    (net (code "74") (name "Net-(Q1-2)") (class "Default")
      (node (ref "Q1") (pin "B") (pinfunction "2_B") (pintype "passive"))
      (node (ref "R12") (pin "2") (pinfunction "2_2") (pintype "passive"))
      (node (ref "R13") (pin "2") (pinfunction "2_2") (pintype "passive"))
    )
    (net (code "75") (name "Net-(Q1-3)") (class "Default")
      (node (ref "Q1") (pin "C") (pinfunction "3_C") (pintype "passive"))
      (node (ref "R14") (pin "1") (pinfunction "1_1") (pintype "passive"))
      (node (ref "R15") (pin "1") (pinfunction "1_1") (pintype "passive"))
    )
    (net (code "76") (name "Net-(Q2-1)") (class "Default")
      (node (ref "Q2") (pin "B") (pinfunction "1_B") (pintype "passive"))
      (node (ref "R15") (pin "2") (pinfunction "2_2") (pintype "passive"))
    )
    (net (code "77") (name "Net-(Q2-2)") (class "Default")
      (node (ref "Q2") (pin "E") (pinfunction "2_E") (pintype "passive"))
      (node (ref "R16") (pin "2") (pinfunction "2_2") (pintype "passive"))
    )
    (net (code "78") (name "Net-(Q3-1)") (class "Default")
      (node (ref "Q3") (pin "B") (pinfunction "1_B") (pintype "passive"))
      (node (ref "R18") (pin "2") (pinfunction "2_2") (pintype "passive"))
    )
    (net (code "79") (name "Net-(Q3-3)") (class "Default")
      (node (ref "Q3") (pin "C") (pinfunction "3_C") (pintype "passive"))
      (node (ref "R19") (pin "2") (pinfunction "2_2") (pintype "passive"))
      (node (ref "R20") (pin "2") (pinfunction "2_2") (pintype "passive"))
      (node (ref "R21") (pin "2") (pinfunction "2_2") (pintype "passive"))
      (node (ref "R22") (pin "2") (pinfunction "2_2") (pintype "passive"))
      (node (ref "R23") (pin "2") (pinfunction "2_2") (pintype "passive"))
      (node (ref "R24") (pin "2") (pinfunction "2_2") (pintype "passive"))
      (node (ref "R25") (pin "2") (pinfunction "2_2") (pintype "passive"))
      (node (ref "R26") (pin "2") (pinfunction "2_2") (pintype "passive"))
      (node (ref "R27") (pin "2") (pinfunction "2_2") (pintype "passive"))
      (node (ref "R28") (pin "2") (pinfunction "2_2") (pintype "passive"))
      (node (ref "R29") (pin "2") (pinfunction "2_2") (pintype "passive"))
      (node (ref "R30") (pin "2") (pinfunction "2_2") (pintype "passive"))
    )
    (net (code "80") (name "Net-(U1-+Vout)") (class "Default")
      (node (ref "L1") (pin "1") (pintype "passive"))
      (node (ref "U1") (pin "3") (pinfunction "+Vout_3") (pintype "passive"))
    )
    (net (code "81") (name "Net-(U2-AVDD1)") (class "Default")
      (node (ref "C10") (pin "1") (pinfunction "1_1") (pintype "passive"))
      (node (ref "C11") (pin "1") (pinfunction "1_1") (pintype "passive"))
      (node (ref "C12") (pin "1") (pinfunction "1_1") (pintype "passive"))
      (node (ref "C13") (pin "1") (pinfunction "1_1") (pintype "passive"))
      (node (ref "C14") (pin "2") (pinfunction "2_2") (pintype "passive"))
      (node (ref "C8") (pin "1") (pinfunction "1_1") (pintype "passive"))
      (node (ref "C9") (pin "1") (pinfunction "1_1") (pintype "passive"))
      (node (ref "R2") (pin "1") (pinfunction "1_1") (pintype "passive"))
      (node (ref "U2") (pin "10") (pinfunction "DVDD2_10") (pintype "power_in"))
      (node (ref "U2") (pin "21") (pinfunction "AVDD5_21") (pintype "power_in"))
      (node (ref "U2") (pin "24") (pinfunction "AVDD3_24") (pintype "power_in"))
      (node (ref "U2") (pin "27") (pinfunction "AVDD2_27") (pintype "power_in"))
      (node (ref "U2") (pin "28") (pinfunction "AVDD1_28") (pintype "power_in"))
      (node (ref "U2") (pin "29") (pinfunction "AVDD4_29") (pintype "power_in"))
      (node (ref "U2") (pin "31") (pinfunction "AVDD6_31") (pintype "power_in"))
      (node (ref "U2") (pin "39") (pinfunction "DVDD1_39") (pintype "power_in"))
    )
    (net (code "82") (name "Net-(U2-DCOUPL)") (class "Default")
      (node (ref "C28") (pin "2") (pinfunction "2_2") (pintype "passive"))
      (node (ref "U2") (pin "40") (pinfunction "DCOUPL_40") (pintype "input"))
    )
    (net (code "83") (name "Net-(U2-P23{slash}OSC32K-Q2)") (class "Default")
      (node (ref "C25") (pin "2") (pinfunction "2_2") (pintype "passive"))
      (node (ref "U2") (pin "33") (pinfunction "P23/OSC32K-Q2_33") (pintype "bidirectional"))
      (node (ref "X1") (pin "1") (pinfunction "1_1") (pintype "passive"))
    )
    (net (code "84") (name "Net-(U2-P24{slash}OSC32K-Q1)") (class "Default")
      (node (ref "C26") (pin "2") (pinfunction "2_2") (pintype "passive"))
      (node (ref "U2") (pin "32") (pinfunction "P24/OSC32K-Q1_32") (pintype "bidirectional"))
      (node (ref "X1") (pin "2") (pinfunction "2_2") (pintype "passive"))
    )
    (net (code "85") (name "Net-(U2-RBIAS)") (class "Default")
      (node (ref "R9") (pin "1") (pinfunction "1_1") (pintype "passive"))
      (node (ref "U2") (pin "30") (pinfunction "RBIAS_30") (pintype "input"))
    )
    (net (code "86") (name "Net-(U2-RF_N)") (class "Default")
      (node (ref "C22") (pin "1") (pinfunction "1_1") (pintype "passive"))
      (node (ref "U2") (pin "26") (pinfunction "RF_N_26") (pintype "output"))
    )
    (net (code "87") (name "Net-(U2-RF_P)") (class "Default")
      (node (ref "C16") (pin "1") (pinfunction "1_1") (pintype "passive"))
      (node (ref "U2") (pin "25") (pinfunction "RF_P_25") (pintype "output"))
    )
    (net (code "88") (name "Net-(U2-XOSC32M_Q1)") (class "Default")
      (node (ref "C24") (pin "2") (pinfunction "2_2") (pintype "passive"))
      (node (ref "U2") (pin "22") (pinfunction "XOSC32M_Q1_22") (pintype "input"))
      (node (ref "X2") (pin "3") (pinfunction "3_3") (pintype "power_in"))
    )
    (net (code "89") (name "Net-(U2-XOSC32M_Q2)") (class "Default")
      (node (ref "C27") (pin "2") (pinfunction "2_2") (pintype "passive"))
      (node (ref "U2") (pin "23") (pinfunction "XOSC32M_Q2_23") (pintype "input"))
      (node (ref "X2") (pin "1") (pinfunction "1_1") (pintype "power_in"))
    )
    (net (code "90") (name "Net-(U3-PWM1)") (class "Default")
      (node (ref "JP4") (pin "1") (pinfunction "1_1") (pintype "passive"))
      (node (ref "U3") (pin "4") (pinfunction "PWM1_4") (pintype "passive"))
    )
    (net (code "91") (name "Net-(U3-PWM2)") (class "Default")
      (node (ref "JP4") (pin "2") (pinfunction "2_2") (pintype "passive"))
      (node (ref "U3") (pin "5") (pinfunction "PWM2_5") (pintype "passive"))
    )
    (net (code "92") (name "Net-(U3-VDD)") (class "Default")
      (node (ref "C23") (pin "1") (pinfunction "1_1") (pintype "passive"))
      (node (ref "R8") (pin "1") (pinfunction "1_1") (pintype "passive"))
      (node (ref "U3") (pin "6") (pinfunction "VDD_6") (pintype "passive"))
    )
    (net (code "93") (name "Net-(U5-X1)") (class "Default")
      (node (ref "C31") (pin "1") (pinfunction "1_1") (pintype "passive"))
      (node (ref "U5") (pin "2") (pinfunction "X1_2") (pintype "passive"))
      (node (ref "X3") (pin "2") (pinfunction "2_2") (pintype "passive"))
    )
    (net (code "94") (name "Net-(U5-X2)") (class "Default")
      (node (ref "C32") (pin "1") (pinfunction "1_1") (pintype "passive"))
      (node (ref "U5") (pin "3") (pinfunction "X2_3") (pintype "passive"))
      (node (ref "X3") (pin "1") (pinfunction "1_1") (pintype "passive"))
    )
    (net (code "95") (name "Net-(U6-CX)") (class "Default")
      (node (ref "C19") (pin "2") (pinfunction "2_2") (pintype "passive"))
      (node (ref "U6") (pin "3") (pinfunction "CX_3") (pintype "passive"))
    )
    (net (code "96") (name "VCC") (class "Default")
      (node (ref "C15") (pin "2") (pinfunction "2_2") (pintype "passive"))
      (node (ref "C18") (pin "2") (pinfunction "2_2") (pintype "passive"))
      (node (ref "C29") (pin "1") (pinfunction "1_1") (pintype "passive"))
      (node (ref "C30") (pin "2") (pinfunction "2_2") (pintype "passive"))
      (node (ref "CN3-1") (pin "1") (pinfunction "1_1") (pintype "passive"))
      (node (ref "JP1") (pin "1") (pinfunction "1_1") (pintype "passive"))
      (node (ref "LED1") (pin "A") (pinfunction "1_A") (pintype "passive"))
      (node (ref "LED10") (pin "A") (pinfunction "1_A") (pintype "passive"))
      (node (ref "LED11") (pin "A") (pinfunction "1_A") (pintype "passive"))
      (node (ref "LED12") (pin "A") (pinfunction "1_A") (pintype "passive"))
      (node (ref "LED2") (pin "A") (pinfunction "1_A") (pintype "passive"))
      (node (ref "LED3") (pin "A") (pinfunction "1_A") (pintype "passive"))
      (node (ref "LED4") (pin "A") (pinfunction "1_A") (pintype "passive"))
      (node (ref "LED5") (pin "A") (pinfunction "1_A") (pintype "passive"))
      (node (ref "LED6") (pin "A") (pinfunction "1_A") (pintype "passive"))
      (node (ref "LED7") (pin "A") (pinfunction "1_A") (pintype "passive"))
      (node (ref "LED8") (pin "A") (pinfunction "1_A") (pintype "passive"))
      (node (ref "LED9") (pin "A") (pinfunction "1_A") (pintype "passive"))
      (node (ref "R1") (pin "2") (pinfunction "2_2") (pintype "passive"))
      (node (ref "R2") (pin "2") (pinfunction "2_2") (pintype "passive"))
      (node (ref "R5") (pin "1") (pinfunction "1_1") (pintype "passive"))
      (node (ref "R7") (pin "1") (pinfunction "1_1") (pintype "passive"))
      (node (ref "R8") (pin "2") (pinfunction "2_2") (pintype "passive"))
      (node (ref "U4") (pin "8") (pinfunction "VCC_8") (pintype "passive"))
      (node (ref "U5") (pin "8") (pinfunction "VCC1_8") (pintype "passive"))
      (node (ref "U6") (pin "1") (pinfunction "VM_1") (pintype "passive"))
      (node (ref "U6") (pin "6") (pinfunction "VDD_6") (pintype "passive"))
    )
    (net (code "97") (name "VDD") (class "Default")
      (node (ref "C5") (pin "2") (pinfunction "2_2") (pintype "passive"))
      (node (ref "C6") (pin "2") (pinfunction "2_2") (pintype "passive"))
      (node (ref "D1") (pin "1") (pinfunction "1_1") (pintype "passive"))
      (node (ref "D2") (pin "1") (pinfunction "1_1") (pintype "passive"))
      (node (ref "Q2") (pin "C") (pinfunction "3_C") (pintype "passive"))
      (node (ref "R14") (pin "2") (pinfunction "2_2") (pintype "passive"))
      (node (ref "U1") (pin "2") (pinfunction "Vin_2") (pintype "passive"))
    )
    (net (code "98") (name "unconnected-(SW-2-PadNO)") (class "Default")
      (node (ref "SW") (pin "NO") (pinfunction "2_NO") (pintype "passive"))
    )
    (net (code "99") (name "unconnected-(U2-NC-Pad4)") (class "Default")
      (node (ref "U2") (pin "4") (pinfunction "NC_4") (pintype "power_in"))
    )
    (net (code "100") (name "unconnected-(U2-P11-Pad9)") (class "Default")
      (node (ref "U2") (pin "9") (pinfunction "P11_9") (pintype "passive"))
    )
    (net (code "101") (name "unconnected-(U3-PA1-Pad2)") (class "Default")
      (node (ref "U3") (pin "2") (pinfunction "PA1_2") (pintype "passive"))
    )
    (net (code "102") (name "unconnected-(U3-PB0-Pad1)") (class "Default")
      (node (ref "U3") (pin "1") (pinfunction "PB0_1") (pintype "passive"))
    )
    (net (code "103") (name "unconnected-(U3-VPP-Pad8)") (class "Default")
      (node (ref "U3") (pin "8") (pinfunction "VPP_8") (pintype "passive"))
    )
    (net (code "104") (name "unconnected-(U5-VCC2-Pad1)") (class "Default")
      (node (ref "U5") (pin "1") (pinfunction "VCC2_1") (pintype "passive"))
    )
  )
)
